# PRTF01.net
KiCad netlist of a schematic drawn in EAGLE
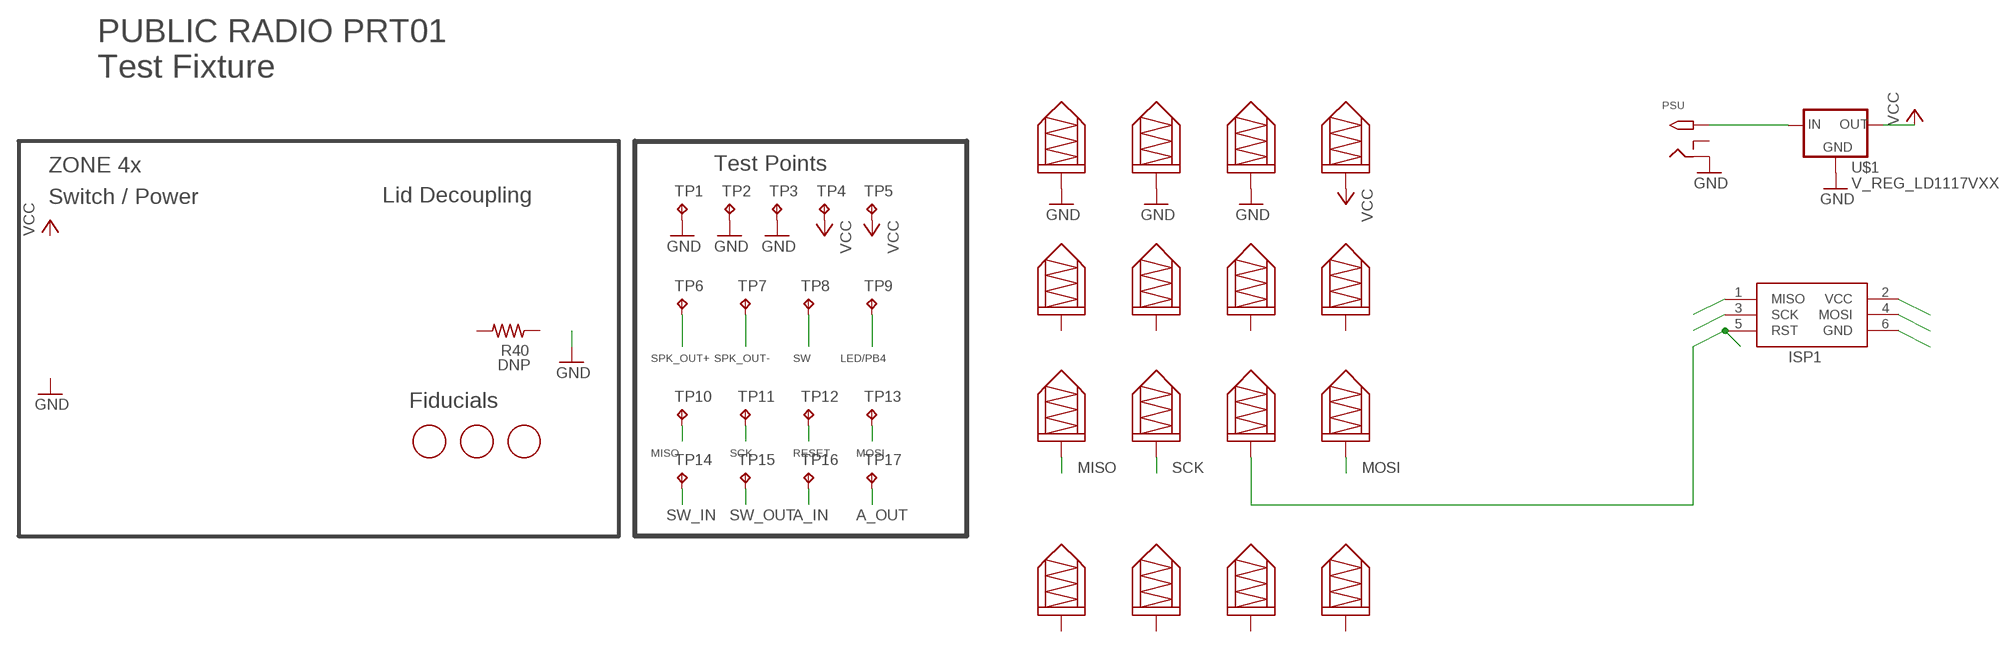
[diagram p0: schematic, sheet 1]

(export (version "E")
  (design (tool "Eeschema 10.0.6"))
  (components
    (comp (ref "ISP1")
      (value "AVRISP-6")
      (footprint "eagle-import:AVRISP")
      (libsource (lib "eagle-import") (part "AVRISP-6"))
    )
    (comp (ref "MARK1")
      (value "FIDUCIAL")
      (footprint "eagle-import:FIDUCIAL_1MM")
      (libsource (lib "eagle-import") (part "FIDUCIAL"))
    )
    (comp (ref "MARK2")
      (value "FIDUCIAL")
      (footprint "eagle-import:FIDUCIAL_1MM")
      (libsource (lib "eagle-import") (part "FIDUCIAL"))
    )
    (comp (ref "MARK3")
      (value "FIDUCIAL")
      (footprint "eagle-import:FIDUCIAL_1MM")
      (libsource (lib "eagle-import") (part "FIDUCIAL"))
    )
    (comp (ref "P1")
      (value "0908MILL_MAX_SPRINGPIN")
      (footprint "eagle-import:0908MILL_MAX_SPRINGPIN")
      (libsource (lib "eagle-import") (part "0908MILL_MAX_SPRINGPIN"))
    )
    (comp (ref "P2")
      (value "0908MILL_MAX_SPRINGPIN")
      (footprint "eagle-import:0908MILL_MAX_SPRINGPIN")
      (libsource (lib "eagle-import") (part "0908MILL_MAX_SPRINGPIN"))
    )
    (comp (ref "P3")
      (value "0908MILL_MAX_SPRINGPIN")
      (footprint "eagle-import:0908MILL_MAX_SPRINGPIN")
      (libsource (lib "eagle-import") (part "0908MILL_MAX_SPRINGPIN"))
    )
    (comp (ref "P4")
      (value "0908MILL_MAX_SPRINGPIN")
      (footprint "eagle-import:0908MILL_MAX_SPRINGPIN")
      (libsource (lib "eagle-import") (part "0908MILL_MAX_SPRINGPIN"))
    )
    (comp (ref "P6")
      (value "0908MILL_MAX_SPRINGPIN")
      (footprint "eagle-import:0908MILL_MAX_SPRINGPIN")
      (libsource (lib "eagle-import") (part "0908MILL_MAX_SPRINGPIN"))
    )
    (comp (ref "P8")
      (value "0908MILL_MAX_SPRINGPIN")
      (footprint "eagle-import:0908MILL_MAX_SPRINGPIN")
      (libsource (lib "eagle-import") (part "0908MILL_MAX_SPRINGPIN"))
    )
    (comp (ref "P9")
      (value "0908MILL_MAX_SPRINGPIN")
      (footprint "eagle-import:0908MILL_MAX_SPRINGPIN")
      (libsource (lib "eagle-import") (part "0908MILL_MAX_SPRINGPIN"))
    )
    (comp (ref "P10")
      (value "0908MILL_MAX_SPRINGPIN")
      (footprint "eagle-import:0908MILL_MAX_SPRINGPIN")
      (libsource (lib "eagle-import") (part "0908MILL_MAX_SPRINGPIN"))
    )
    (comp (ref "P11")
      (value "0908MILL_MAX_SPRINGPIN")
      (footprint "eagle-import:0908MILL_MAX_SPRINGPIN")
      (libsource (lib "eagle-import") (part "0908MILL_MAX_SPRINGPIN"))
    )
    (comp (ref "P12")
      (value "0908MILL_MAX_SPRINGPIN")
      (footprint "eagle-import:0908MILL_MAX_SPRINGPIN")
      (libsource (lib "eagle-import") (part "0908MILL_MAX_SPRINGPIN"))
    )
    (comp (ref "P13")
      (value "0908MILL_MAX_SPRINGPIN")
      (footprint "eagle-import:0908MILL_MAX_SPRINGPIN")
      (libsource (lib "eagle-import") (part "0908MILL_MAX_SPRINGPIN"))
    )
    (comp (ref "P14")
      (value "0908MILL_MAX_SPRINGPIN")
      (footprint "eagle-import:0908MILL_MAX_SPRINGPIN")
      (libsource (lib "eagle-import") (part "0908MILL_MAX_SPRINGPIN"))
    )
    (comp (ref "P15")
      (value "0908MILL_MAX_SPRINGPIN")
      (footprint "eagle-import:0908MILL_MAX_SPRINGPIN")
      (libsource (lib "eagle-import") (part "0908MILL_MAX_SPRINGPIN"))
    )
    (comp (ref "P16")
      (value "0908MILL_MAX_SPRINGPIN")
      (footprint "eagle-import:0908MILL_MAX_SPRINGPIN")
      (libsource (lib "eagle-import") (part "0908MILL_MAX_SPRINGPIN"))
    )
    (comp (ref "P17")
      (value "0908MILL_MAX_SPRINGPIN")
      (footprint "eagle-import:0908MILL_MAX_SPRINGPIN")
      (libsource (lib "eagle-import") (part "0908MILL_MAX_SPRINGPIN"))
    )
    (comp (ref "PSU")
      (value "2.1MMJACKTHM")
      (footprint "eagle-import:PJ-102A")
      (libsource (lib "eagle-import") (part "2.1MMJACKTHM"))
    )
    (comp (ref "R40")
      (value "DNP")
      (footprint "eagle-import:0603_CPL")
      (fields (field (name "MFG_PN") "ERJ-3GEY0R00V"))
      (libsource (lib "eagle-import") (part "R_SMT_R0603_CPL"))
    )
    (comp (ref "TP1")
      (value "TPTP20R")
      (footprint "eagle-import:TP20R")
      (libsource (lib "eagle-import") (part "TPTP20R"))
    )
    (comp (ref "TP2")
      (value "TPTP20R")
      (footprint "eagle-import:TP20R")
      (libsource (lib "eagle-import") (part "TPTP20R"))
    )
    (comp (ref "TP3")
      (value "TPTP20R")
      (footprint "eagle-import:TP20R")
      (libsource (lib "eagle-import") (part "TPTP20R"))
    )
    (comp (ref "TP4")
      (value "TPTP20R")
      (footprint "eagle-import:TP20R")
      (libsource (lib "eagle-import") (part "TPTP20R"))
    )
    (comp (ref "TP5")
      (value "TPTP20R")
      (footprint "eagle-import:TP20R")
      (libsource (lib "eagle-import") (part "TPTP20R"))
    )
    (comp (ref "TP6")
      (value "TPTP20R")
      (footprint "eagle-import:TP20R")
      (libsource (lib "eagle-import") (part "TPTP20R"))
    )
    (comp (ref "TP7")
      (value "TPTP20R")
      (footprint "eagle-import:TP20R")
      (libsource (lib "eagle-import") (part "TPTP20R"))
    )
    (comp (ref "TP8")
      (value "TPTP20R")
      (footprint "eagle-import:TP20R")
      (libsource (lib "eagle-import") (part "TPTP20R"))
    )
    (comp (ref "TP9")
      (value "TPTP20R")
      (footprint "eagle-import:TP20R")
      (libsource (lib "eagle-import") (part "TPTP20R"))
    )
    (comp (ref "TP10")
      (value "TPTP20R")
      (footprint "eagle-import:TP20R")
      (libsource (lib "eagle-import") (part "TPTP20R"))
    )
    (comp (ref "TP11")
      (value "TPTP20R")
      (footprint "eagle-import:TP20R")
      (libsource (lib "eagle-import") (part "TPTP20R"))
    )
    (comp (ref "TP12")
      (value "TPTP20R")
      (footprint "eagle-import:TP20R")
      (libsource (lib "eagle-import") (part "TPTP20R"))
    )
    (comp (ref "TP13")
      (value "TPTP20R")
      (footprint "eagle-import:TP20R")
      (libsource (lib "eagle-import") (part "TPTP20R"))
    )
    (comp (ref "TP14")
      (value "TPTP20R")
      (footprint "eagle-import:TP20R")
      (libsource (lib "eagle-import") (part "TPTP20R"))
    )
    (comp (ref "TP15")
      (value "TPTP20R")
      (footprint "eagle-import:TP20R")
      (libsource (lib "eagle-import") (part "TPTP20R"))
    )
    (comp (ref "TP16")
      (value "TPTP20R")
      (footprint "eagle-import:TP20R")
      (libsource (lib "eagle-import") (part "TPTP20R"))
    )
    (comp (ref "TP17")
      (value "TPTP20R")
      (footprint "eagle-import:TP20R")
      (libsource (lib "eagle-import") (part "TPTP20R"))
    )
    (comp (ref "U$1")
      (value "V_REG_LD1117VXX")
      (footprint "eagle-import:78XXL")
      (libsource (lib "eagle-import") (part "V_REG_LD1117VXX"))
    )
    (comp (ref "U$P7")
      (value "0908MILL_MAX_SPRINGPIN")
      (footprint "eagle-import:0908MILL_MAX_SPRINGPIN")
      (libsource (lib "eagle-import") (part "0908MILL_MAX_SPRINGPIN"))
    )
  )
  (nets
    (net (code "1") (name "/A_IN") (class "Default")
      (node (ref "TP16") (pin "TP") (pinfunction "TP_TP") (pintype "input"))
    )
    (net (code "2") (name "/A_OUT") (class "Default")
      (node (ref "TP17") (pin "TP") (pinfunction "TP_TP") (pintype "input"))
    )
    (net (code "3") (name "/LED{slash}PB4") (class "Default")
      (node (ref "TP9") (pin "TP") (pinfunction "TP_TP") (pintype "input"))
    )
    (net (code "4") (name "/MISO") (class "Default")
      (node (ref "ISP1") (pin "1") (pinfunction "MISO_1") (pintype "input"))
      (node (ref "P10") (pin "P$1") (pinfunction "P$1_P$1") (pintype "bidirectional"))
    )
    (net (code "5") (name "/MOSI") (class "Default")
      (node (ref "ISP1") (pin "4") (pinfunction "MOSI_4") (pintype "output"))
      (node (ref "P13") (pin "P$1") (pinfunction "P$1_P$1") (pintype "bidirectional"))
    )
    (net (code "6") (name "/RESET") (class "Default")
      (node (ref "ISP1") (pin "5") (pinfunction "RST_5") (pintype "output"))
      (node (ref "P12") (pin "P$1") (pinfunction "P$1_P$1") (pintype "bidirectional"))
      (node (ref "TP12") (pin "TP") (pinfunction "TP_TP") (pintype "input"))
    )
    (net (code "7") (name "/SCK") (class "Default")
      (node (ref "ISP1") (pin "3") (pinfunction "SCK_3") (pintype "output"))
      (node (ref "P11") (pin "P$1") (pinfunction "P$1_P$1") (pintype "bidirectional"))
    )
    (net (code "8") (name "/SPK_OUT+") (class "Default")
      (node (ref "TP6") (pin "TP") (pinfunction "TP_TP") (pintype "input"))
    )
    (net (code "9") (name "/SPK_OUT-") (class "Default")
      (node (ref "TP7") (pin "TP") (pinfunction "TP_TP") (pintype "input"))
    )
    (net (code "10") (name "/SW") (class "Default")
      (node (ref "TP8") (pin "TP") (pinfunction "TP_TP") (pintype "input"))
    )
    (net (code "11") (name "/SW_IN") (class "Default")
      (node (ref "TP14") (pin "TP") (pinfunction "TP_TP") (pintype "input"))
    )
    (net (code "12") (name "/SW_OUT") (class "Default")
      (node (ref "TP15") (pin "TP") (pinfunction "TP_TP") (pintype "input"))
    )
    (net (code "13") (name "GND") (class "Default")
      (node (ref "P1") (pin "P$1") (pinfunction "P$1_P$1") (pintype "bidirectional"))
      (node (ref "P2") (pin "P$1") (pinfunction "P$1_P$1") (pintype "bidirectional"))
      (node (ref "P3") (pin "P$1") (pinfunction "P$1_P$1") (pintype "bidirectional"))
      (node (ref "PSU") (pin "RING") (pinfunction "RING_RING") (pintype "bidirectional"))
      (node (ref "TP1") (pin "TP") (pinfunction "TP_TP") (pintype "input"))
      (node (ref "TP2") (pin "TP") (pinfunction "TP_TP") (pintype "input"))
      (node (ref "TP3") (pin "TP") (pinfunction "TP_TP") (pintype "input"))
      (node (ref "U$1") (pin "IN") (pinfunction "GND_IN") (pintype "input"))
    )
    (net (code "14") (name "Net-(U$1-IN)") (class "Default")
      (node (ref "PSU") (pin "TIP") (pinfunction "TIP_TIP") (pintype "bidirectional"))
      (node (ref "U$1") (pin "OUT") (pinfunction "IN_OUT") (pintype "input"))
    )
    (net (code "15") (name "VCC") (class "Default")
      (node (ref "P4") (pin "P$1") (pinfunction "P$1_P$1") (pintype "bidirectional"))
      (node (ref "TP4") (pin "TP") (pinfunction "TP_TP") (pintype "input"))
      (node (ref "TP5") (pin "TP") (pinfunction "TP_TP") (pintype "input"))
      (node (ref "U$1") (pin "GND") (pinfunction "OUT_GND") (pintype "output"))
    )
    (net (code "16") (name "unconnected-(ISP1-GND-Pad6)") (class "Default")
      (node (ref "ISP1") (pin "6") (pinfunction "GND_6") (pintype "power_in"))
    )
    (net (code "17") (name "unconnected-(ISP1-VCC-Pad2)") (class "Default")
      (node (ref "ISP1") (pin "2") (pinfunction "VCC_2") (pintype "power_in"))
    )
    (net (code "18") (name "unconnected-(P6-PadP$1)") (class "Default")
      (node (ref "P6") (pin "P$1") (pinfunction "P$1_P$1") (pintype "bidirectional"))
    )
    (net (code "19") (name "unconnected-(P8-PadP$1)") (class "Default")
      (node (ref "P8") (pin "P$1") (pinfunction "P$1_P$1") (pintype "bidirectional"))
    )
    (net (code "20") (name "unconnected-(P9-PadP$1)") (class "Default")
      (node (ref "P9") (pin "P$1") (pinfunction "P$1_P$1") (pintype "bidirectional"))
    )
    (net (code "21") (name "unconnected-(P14-PadP$1)") (class "Default")
      (node (ref "P14") (pin "P$1") (pinfunction "P$1_P$1") (pintype "bidirectional"))
    )
    (net (code "22") (name "unconnected-(P15-PadP$1)") (class "Default")
      (node (ref "P15") (pin "P$1") (pinfunction "P$1_P$1") (pintype "bidirectional"))
    )
    (net (code "23") (name "unconnected-(P16-PadP$1)") (class "Default")
      (node (ref "P16") (pin "P$1") (pinfunction "P$1_P$1") (pintype "bidirectional"))
    )
    (net (code "24") (name "unconnected-(P17-PadP$1)") (class "Default")
      (node (ref "P17") (pin "P$1") (pinfunction "P$1_P$1") (pintype "bidirectional"))
    )
    (net (code "25") (name "unconnected-(PSU-PadRING_SW)") (class "Default")
      (node (ref "PSU") (pin "RING_SW") (pinfunction "RING_SW_RING_SW") (pintype "bidirectional"))
    )
    (net (code "26") (name "unconnected-(R40-Pad1)") (class "Default")
      (node (ref "R40") (pin "1") (pinfunction "1_1") (pintype "passive"))
    )
    (net (code "27") (name "unconnected-(R40-Pad2)") (class "Default")
      (node (ref "R40") (pin "2") (pinfunction "2_2") (pintype "passive"))
    )
    (net (code "28") (name "unconnected-(TP10-PadTP)") (class "Default")
      (node (ref "TP10") (pin "TP") (pinfunction "TP_TP") (pintype "input"))
    )
    (net (code "29") (name "unconnected-(TP11-PadTP)") (class "Default")
      (node (ref "TP11") (pin "TP") (pinfunction "TP_TP") (pintype "input"))
    )
    (net (code "30") (name "unconnected-(TP13-PadTP)") (class "Default")
      (node (ref "TP13") (pin "TP") (pinfunction "TP_TP") (pintype "input"))
    )
    (net (code "31") (name "unconnected-(U$P7-PadP$1)") (class "Default")
      (node (ref "U$P7") (pin "P$1") (pinfunction "P$1_P$1") (pintype "bidirectional"))
    )
  )
)
